# MCP2551T.net
KiCad netlist of a schematic drawn in Altium Designer
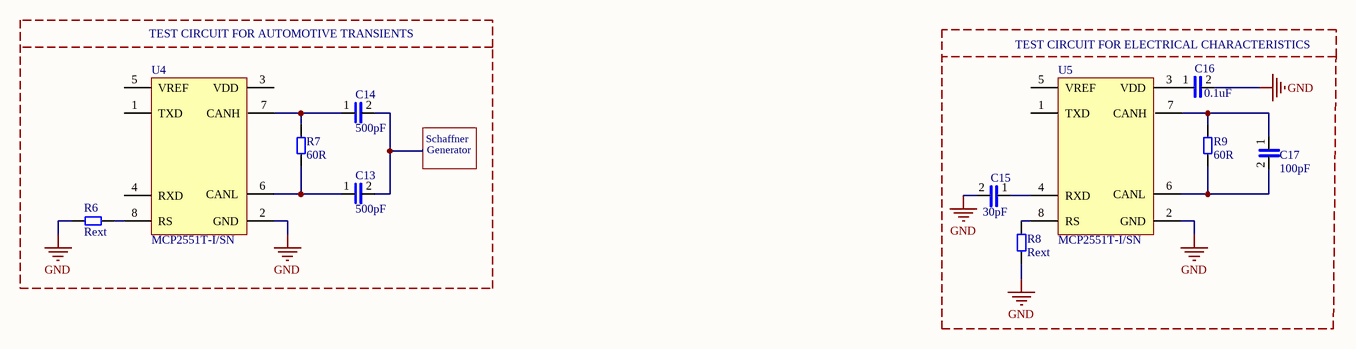
[diagram p0: MCP2551T.SchDoc]

(export (version "E")
  (design (tool "Eeschema 10.0.6"))
  (components
    (comp (ref "C13")
      (value "500pF")
      (footprint "CAP-0805-NP0")
      (description "CAP CER 3300PF 50V NPO 0805")
      (fields
        (field (name "MANUFACTURER") "Yageo")
        (field (name "MANUFACTURER PART NUMBER") "CC0805JKNPO9BN332")
      )
      (libsource (lib "Schlib1") (part "CAP-0805-NP0-3.3nF"))
    )
    (comp (ref "C14")
      (value "500pF")
      (footprint "CAP-0805-NP0")
      (description "CAP CER 3300PF 50V NPO 0805")
      (fields
        (field (name "MANUFACTURER") "Yageo")
        (field (name "MANUFACTURER PART NUMBER") "CC0805JKNPO9BN332")
      )
      (libsource (lib "Schlib1") (part "CAP-0805-NP0-3.3nF"))
    )
    (comp (ref "C15")
      (value "30pF")
      (footprint "CAP-0805-NP0")
      (description "CAP CER 3300PF 50V NPO 0805")
      (fields
        (field (name "MANUFACTURER") "Yageo")
        (field (name "MANUFACTURER PART NUMBER") "CC0805JKNPO9BN332")
      )
      (libsource (lib "") (part "CAP-0805-NP0-3.3nF_1"))
    )
    (comp (ref "C16")
      (value "0.1uF")
      (footprint "CAP-0805-NP0")
      (description "CAP CER 3300PF 50V NPO 0805")
      (fields
        (field (name "MANUFACTURER") "Yageo")
        (field (name "MANUFACTURER PART NUMBER") "CC0805JKNPO9BN332")
      )
      (libsource (lib "Schlib1") (part "CAP-0805-NP0-3.3nF"))
    )
    (comp (ref "C17")
      (value "100pF")
      (footprint "CAP-0805-NP0")
      (description "CAP CER 3300PF 50V NPO 0805")
      (fields
        (field (name "MANUFACTURER") "Yageo")
        (field (name "MANUFACTURER PART NUMBER") "CC0805JKNPO9BN332")
      )
      (libsource (lib "") (part "CAP-0805-NP0-3.3nF_2"))
    )
    (comp (ref "R6")
      (value "Rext")
      (footprint "RES-0805")
      (description "Res SMD 0805 10K 1% 0.125W T.C.100PPM")
      (fields
        (field (name "MANUFACTURER") "Yageo")
        (field (name "MANUFACTURER PART NUMBER") "RC0805FR-0710KL")
      )
      (libsource (lib "Schlib1") (part "RES-0805-10k"))
    )
    (comp (ref "R7")
      (value "60R")
      (footprint "RES-0805")
      (description "Res SMD 0805 10K 1% 0.125W T.C.100PPM")
      (fields
        (field (name "MANUFACTURER") "Yageo")
        (field (name "MANUFACTURER PART NUMBER") "RC0805FR-0710KL")
      )
      (libsource (lib "Schlib1") (part "RES-0805-10k"))
    )
    (comp (ref "R8")
      (value "Rext")
      (footprint "RES-0805")
      (description "Res SMD 0805 10K 1% 0.125W T.C.100PPM")
      (fields
        (field (name "MANUFACTURER") "Yageo")
        (field (name "MANUFACTURER PART NUMBER") "RC0805FR-0710KL")
      )
      (libsource (lib "Schlib1") (part "RES-0805-10k"))
    )
    (comp (ref "R9")
      (value "60R")
      (footprint "RES-0805")
      (description "Res SMD 0805 10K 1% 0.125W T.C.100PPM")
      (fields
        (field (name "MANUFACTURER") "Yageo")
        (field (name "MANUFACTURER PART NUMBER") "RC0805FR-0710KL")
      )
      (libsource (lib "Schlib1") (part "RES-0805-10k"))
    )
    (comp (ref "U4")
      (value "MCP2551T-I/SN")
      (footprint "MCP2551T")
      (description "1/1 Transceiver Half CAN 8-SOIC")
      (fields
        (field (name "MANUFACTURER") "Microchip")
        (field (name "MANUFACTURER PART NUMBER") "MCP2551-I/SN")
      )
      (libsource (lib "Schlib1") (part "MCP2551T-I/SN"))
    )
    (comp (ref "U5")
      (value "MCP2551T-I/SN")
      (footprint "MCP2551T")
      (description "1/1 Transceiver Half CAN 8-SOIC")
      (fields
        (field (name "MANUFACTURER") "Microchip")
        (field (name "MANUFACTURER PART NUMBER") "MCP2551-I/SN")
      )
      (libsource (lib "Schlib1") (part "MCP2551T-I/SN"))
    )
  )
  (nets
    (net (code "1") (name "GND") (class "Default")
      (node (ref "C15") (pin "2") (pinfunction "2_2") (pintype "passive"))
      (node (ref "C16") (pin "2") (pinfunction "2_2") (pintype "passive"))
      (node (ref "R6") (pin "1") (pinfunction "1_1") (pintype "passive"))
      (node (ref "R8") (pin "1") (pinfunction "1_1") (pintype "passive"))
      (node (ref "U4") (pin "2") (pinfunction "GND_2") (pintype "passive"))
      (node (ref "U5") (pin "2") (pinfunction "GND_2") (pintype "passive"))
    )
    (net (code "2") (name "Net-(C13-Pad2)") (class "Default")
      (node (ref "C13") (pin "2") (pinfunction "2_2") (pintype "passive"))
      (node (ref "C14") (pin "2") (pinfunction "2_2") (pintype "passive"))
    )
    (net (code "3") (name "Net-(U4-CANH)") (class "Default")
      (node (ref "C14") (pin "1") (pinfunction "1_1") (pintype "passive"))
      (node (ref "R7") (pin "2") (pinfunction "2_2") (pintype "passive"))
      (node (ref "U4") (pin "7") (pinfunction "CANH_7") (pintype "passive"))
    )
    (net (code "4") (name "Net-(U4-CANL)") (class "Default")
      (node (ref "C13") (pin "1") (pinfunction "1_1") (pintype "passive"))
      (node (ref "R7") (pin "1") (pinfunction "1_1") (pintype "passive"))
      (node (ref "U4") (pin "6") (pinfunction "CANL_6") (pintype "passive"))
    )
    (net (code "5") (name "Net-(U4-RS)") (class "Default")
      (node (ref "R6") (pin "2") (pinfunction "2_2") (pintype "passive"))
      (node (ref "U4") (pin "8") (pinfunction "RS_8") (pintype "passive"))
    )
    (net (code "6") (name "Net-(U5-CANH)") (class "Default")
      (node (ref "C17") (pin "1") (pinfunction "1_1") (pintype "passive"))
      (node (ref "R9") (pin "2") (pinfunction "2_2") (pintype "passive"))
      (node (ref "U5") (pin "7") (pinfunction "CANH_7") (pintype "passive"))
    )
    (net (code "7") (name "Net-(U5-CANL)") (class "Default")
      (node (ref "C17") (pin "2") (pinfunction "2_2") (pintype "passive"))
      (node (ref "R9") (pin "1") (pinfunction "1_1") (pintype "passive"))
      (node (ref "U5") (pin "6") (pinfunction "CANL_6") (pintype "passive"))
    )
    (net (code "8") (name "Net-(U5-RS)") (class "Default")
      (node (ref "R8") (pin "2") (pinfunction "2_2") (pintype "passive"))
      (node (ref "U5") (pin "8") (pinfunction "RS_8") (pintype "passive"))
    )
    (net (code "9") (name "Net-(U5-RXD)") (class "Default")
      (node (ref "C15") (pin "1") (pinfunction "1_1") (pintype "passive"))
      (node (ref "U5") (pin "4") (pinfunction "RXD_4") (pintype "passive"))
    )
    (net (code "10") (name "Net-(U5-VDD)") (class "Default")
      (node (ref "C16") (pin "1") (pinfunction "1_1") (pintype "passive"))
      (node (ref "U5") (pin "3") (pinfunction "VDD_3") (pintype "passive"))
    )
    (net (code "11") (name "unconnected-(U4-RXD-Pad4)") (class "Default")
      (node (ref "U4") (pin "4") (pinfunction "RXD_4") (pintype "passive"))
    )
    (net (code "12") (name "unconnected-(U4-TXD-Pad1)") (class "Default")
      (node (ref "U4") (pin "1") (pinfunction "TXD_1") (pintype "passive"))
    )
    (net (code "13") (name "unconnected-(U4-VDD-Pad3)") (class "Default")
      (node (ref "U4") (pin "3") (pinfunction "VDD_3") (pintype "passive"))
    )
    (net (code "14") (name "unconnected-(U4-VREF-Pad5)") (class "Default")
      (node (ref "U4") (pin "5") (pinfunction "VREF_5") (pintype "power_in"))
    )
    (net (code "15") (name "unconnected-(U5-TXD-Pad1)") (class "Default")
      (node (ref "U5") (pin "1") (pinfunction "TXD_1") (pintype "passive"))
    )
    (net (code "16") (name "unconnected-(U5-VREF-Pad5)") (class "Default")
      (node (ref "U5") (pin "5") (pinfunction "VREF_5") (pintype "power_in"))
    )
  )
)
